# breakoutWithPH.net
KiCad netlist of a schematic drawn in EAGLE
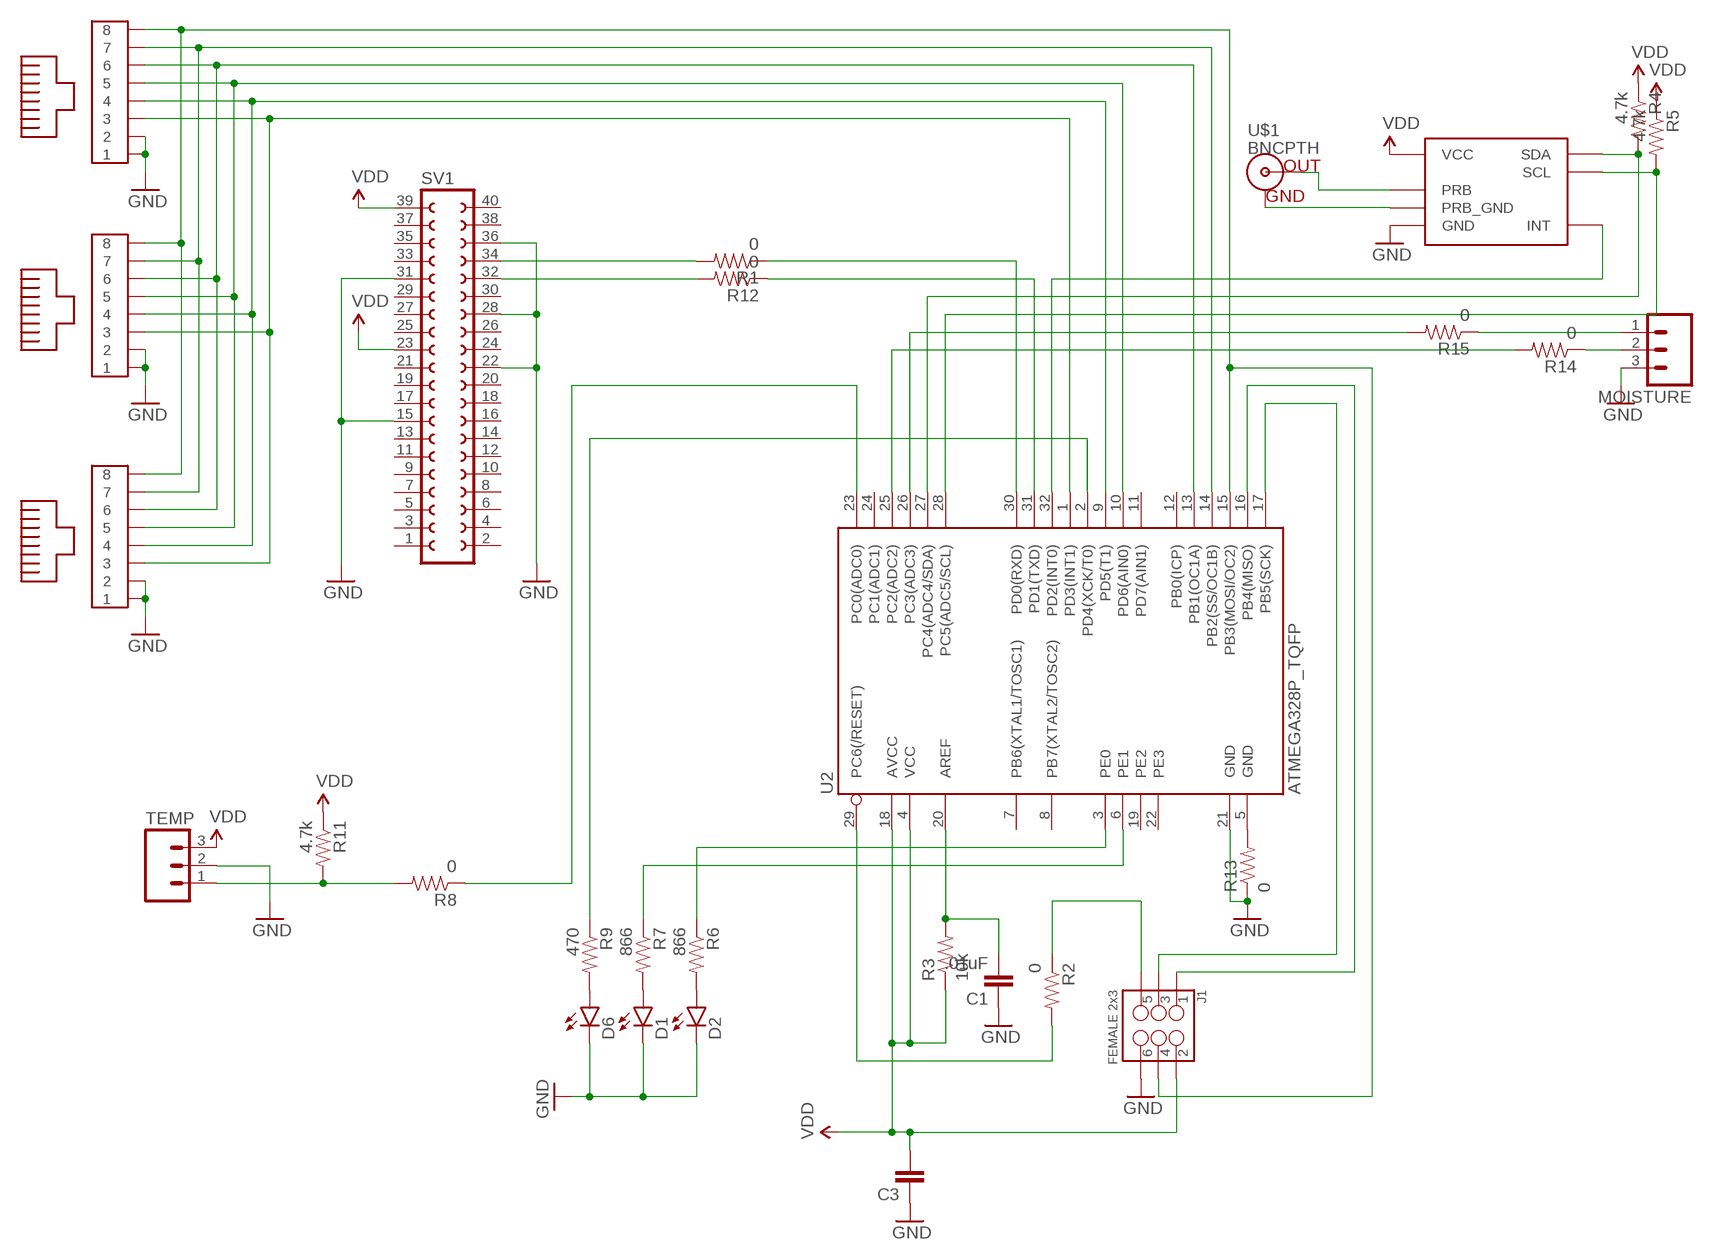
[diagram p0: schematic, sheet 1]

(export (version "E")
  (design (tool "Eeschema 10.0.6"))
  (components
    (comp (ref "C1")
      (value ".01uF")
      (footprint "eagle-import:1206")
      (libsource (lib "eagle-import") (part "CAP1206"))
    )
    (comp (ref "C3")
      (value "CAP1206")
      (footprint "eagle-import:1206")
      (libsource (lib "eagle-import") (part "CAP1206"))
    )
    (comp (ref "D1")
      (value "LED0603")
      (footprint "eagle-import:LED-0603")
      (libsource (lib "eagle-import") (part "LED0603"))
    )
    (comp (ref "D2")
      (value "LED0603")
      (footprint "eagle-import:LED-0603")
      (libsource (lib "eagle-import") (part "LED0603"))
    )
    (comp (ref "D6")
      (value "LED0603")
      (footprint "eagle-import:LED-0603")
      (libsource (lib "eagle-import") (part "LED0603"))
    )
    (comp (ref "J1")
      (value "FEMALE 2x3")
      (footprint "eagle-import:2X3")
      (libsource (lib "eagle-import") (part "M03X2FEMALE"))
    )
    (comp (ref "MOISTURE")
      (value "M03LOCK_LONGPADS")
      (footprint "eagle-import:1X03_LOCK_LONGPADS")
      (libsource (lib "eagle-import") (part "M03LOCK_LONGPADS"))
    )
    (comp (ref "R1")
      (value "0")
      (footprint "eagle-import:1206")
      (libsource (lib "eagle-import") (part "RESISTOR1206"))
    )
    (comp (ref "R2")
      (value "0")
      (footprint "eagle-import:1206")
      (libsource (lib "eagle-import") (part "RESISTOR1206"))
    )
    (comp (ref "R3")
      (value "10k")
      (footprint "eagle-import:1206")
      (libsource (lib "eagle-import") (part "RESISTOR1206"))
    )
    (comp (ref "R4")
      (value "4.7k")
      (footprint "eagle-import:1206")
      (libsource (lib "eagle-import") (part "RESISTOR1206"))
    )
    (comp (ref "R5")
      (value "4.7k")
      (footprint "eagle-import:1206")
      (libsource (lib "eagle-import") (part "RESISTOR1206"))
    )
    (comp (ref "R6")
      (value "866")
      (footprint "eagle-import:1206")
      (libsource (lib "eagle-import") (part "RESISTOR1206"))
    )
    (comp (ref "R7")
      (value "866")
      (footprint "eagle-import:1206")
      (libsource (lib "eagle-import") (part "RESISTOR1206"))
    )
    (comp (ref "R8")
      (value "0")
      (footprint "eagle-import:1206")
      (libsource (lib "eagle-import") (part "RESISTOR1206"))
    )
    (comp (ref "R9")
      (value "470")
      (footprint "eagle-import:1206")
      (libsource (lib "eagle-import") (part "RESISTOR1206"))
    )
    (comp (ref "R11")
      (value "4.7k")
      (footprint "eagle-import:1206")
      (libsource (lib "eagle-import") (part "RESISTOR1206"))
    )
    (comp (ref "R12")
      (value "0")
      (footprint "eagle-import:1206")
      (libsource (lib "eagle-import") (part "RESISTOR1206"))
    )
    (comp (ref "R13")
      (value "0")
      (footprint "eagle-import:1206")
      (libsource (lib "eagle-import") (part "RESISTOR1206"))
    )
    (comp (ref "R14")
      (value "0")
      (footprint "eagle-import:1206")
      (libsource (lib "eagle-import") (part "RESISTOR1206"))
    )
    (comp (ref "R15")
      (value "0")
      (footprint "eagle-import:1206")
      (libsource (lib "eagle-import") (part "RESISTOR1206"))
    )
    (comp (ref "SV1")
      (value "FE20-2")
      (footprint "eagle-import:FE20-2")
      (libsource (lib "eagle-import") (part "FE20-2"))
    )
    (comp (ref "TEMP")
      (value "M03LOCK_LONGPADS")
      (footprint "eagle-import:1X03_LOCK_LONGPADS")
      (libsource (lib "eagle-import") (part "M03LOCK_LONGPADS"))
    )
    (comp (ref "U$1")
      (value "BNCPTH")
      (footprint "eagle-import:BNC")
      (libsource (lib "eagle-import") (part "BNCPTH"))
    )
    (comp (ref "U$2")
      (value "MOLEX-RJ45-SMT")
      (footprint "eagle-import:MOLEX-RJ45-SMT")
      (libsource (lib "eagle-import") (part "MOLEX-RJ45-SMT"))
    )
    (comp (ref "U$3")
      (value "MOLEX-RJ45-SMT")
      (footprint "eagle-import:MOLEX-RJ45-SMT")
      (libsource (lib "eagle-import") (part "MOLEX-RJ45-SMT"))
    )
    (comp (ref "U$4")
      (value "MOLEX-RJ45-SMT")
      (footprint "eagle-import:MOLEX-RJ45-SMT")
      (libsource (lib "eagle-import") (part "MOLEX-RJ45-SMT"))
    )
    (comp (ref "U1")
      (value "PH_SMD")
      (footprint "eagle-import:PH_SMD")
      (libsource (lib "eagle-import") (part "PH_SMD"))
    )
    (comp (ref "U2")
      (value "ATMEGA328P_TQFP")
      (footprint "eagle-import:TQFP32-08")
      (libsource (lib "eagle-import") (part "ATMEGA328P_TQFP"))
    )
  )
  (nets
    (net (code "1") (name "GND") (class "Default")
      (node (ref "C1") (pin "1") (pinfunction "1_1") (pintype "passive"))
      (node (ref "C3") (pin "1") (pinfunction "1_1") (pintype "passive"))
      (node (ref "D1") (pin "C") (pinfunction "C_C") (pintype "passive"))
      (node (ref "D2") (pin "C") (pinfunction "C_C") (pintype "passive"))
      (node (ref "D6") (pin "C") (pinfunction "C_C") (pintype "passive"))
      (node (ref "J1") (pin "6") (pinfunction "6_6") (pintype "bidirectional"))
      (node (ref "MOISTURE") (pin "3") (pinfunction "3_3") (pintype "passive"))
      (node (ref "R13") (pin "1") (pinfunction "1_1") (pintype "passive"))
      (node (ref "SV1") (pin "15") (pinfunction "15_15") (pintype "passive"))
      (node (ref "SV1") (pin "22") (pinfunction "22_22") (pintype "passive"))
      (node (ref "SV1") (pin "28") (pinfunction "28_28") (pintype "passive"))
      (node (ref "SV1") (pin "31") (pinfunction "31_31") (pintype "passive"))
      (node (ref "SV1") (pin "36") (pinfunction "36_36") (pintype "passive"))
      (node (ref "TEMP") (pin "2") (pinfunction "2_2") (pintype "passive"))
      (node (ref "U$2") (pin "1") (pinfunction "1_1") (pintype "bidirectional"))
      (node (ref "U$2") (pin "2") (pinfunction "2_2") (pintype "bidirectional"))
      (node (ref "U$3") (pin "1") (pinfunction "1_1") (pintype "bidirectional"))
      (node (ref "U$3") (pin "2") (pinfunction "2_2") (pintype "bidirectional"))
      (node (ref "U$4") (pin "1") (pinfunction "1_1") (pintype "bidirectional"))
      (node (ref "U$4") (pin "2") (pinfunction "2_2") (pintype "bidirectional"))
      (node (ref "U1") (pin "6") (pinfunction "GND_6") (pintype "power_in"))
      (node (ref "U2") (pin "21") (pinfunction "GND_21") (pintype "bidirectional"))
    )
    (net (code "2") (name "Net-(D1-PadA)") (class "Default")
      (node (ref "D1") (pin "A") (pinfunction "A_A") (pintype "passive"))
      (node (ref "R7") (pin "2") (pinfunction "2_2") (pintype "passive"))
    )
    (net (code "3") (name "Net-(D2-PadA)") (class "Default")
      (node (ref "D2") (pin "A") (pinfunction "A_A") (pintype "passive"))
      (node (ref "R6") (pin "2") (pinfunction "2_2") (pintype "passive"))
    )
    (net (code "4") (name "Net-(D6-PadA)") (class "Default")
      (node (ref "D6") (pin "A") (pinfunction "A_A") (pintype "passive"))
      (node (ref "R9") (pin "2") (pinfunction "2_2") (pintype "passive"))
    )
    (net (code "5") (name "Net-(J1-Pad5)") (class "Default")
      (node (ref "J1") (pin "5") (pinfunction "5_5") (pintype "bidirectional"))
      (node (ref "R2") (pin "1") (pinfunction "1_1") (pintype "passive"))
    )
    (net (code "6") (name "Net-(MOISTURE-Pad1)") (class "Default")
      (node (ref "MOISTURE") (pin "1") (pinfunction "1_1") (pintype "passive"))
      (node (ref "R15") (pin "1") (pinfunction "1_1") (pintype "passive"))
    )
    (net (code "7") (name "Net-(MOISTURE-Pad2)") (class "Default")
      (node (ref "MOISTURE") (pin "2") (pinfunction "2_2") (pintype "passive"))
      (node (ref "R14") (pin "1") (pinfunction "1_1") (pintype "passive"))
    )
    (net (code "8") (name "Net-(R1-Pad2)") (class "Default")
      (node (ref "R1") (pin "2") (pinfunction "2_2") (pintype "passive"))
      (node (ref "SV1") (pin "34") (pinfunction "34_34") (pintype "passive"))
    )
    (net (code "9") (name "Net-(R11-Pad2)") (class "Default")
      (node (ref "R11") (pin "2") (pinfunction "2_2") (pintype "passive"))
      (node (ref "R8") (pin "2") (pinfunction "2_2") (pintype "passive"))
      (node (ref "TEMP") (pin "1") (pinfunction "1_1") (pintype "passive"))
    )
    (net (code "10") (name "Net-(R12-Pad2)") (class "Default")
      (node (ref "R12") (pin "2") (pinfunction "2_2") (pintype "passive"))
      (node (ref "SV1") (pin "32") (pinfunction "32_32") (pintype "passive"))
    )
    (net (code "11") (name "Net-(R13-Pad2)") (class "Default")
      (node (ref "R13") (pin "2") (pinfunction "2_2") (pintype "passive"))
      (node (ref "U2") (pin "5") (pinfunction "GND_5") (pintype "bidirectional"))
    )
    (net (code "12") (name "Net-(U$1-OUT)") (class "Default")
      (node (ref "U$1") (pin "S") (pinfunction "OUT_S") (pintype "bidirectional"))
      (node (ref "U1") (pin "4") (pinfunction "PRB_4") (pintype "bidirectional"))
    )
    (net (code "13") (name "Net-(U1-INT)") (class "Default")
      (node (ref "U1") (pin "7") (pinfunction "INT_7") (pintype "bidirectional"))
      (node (ref "U2") (pin "32") (pinfunction "PD2(INT0)_32") (pintype "bidirectional"))
    )
    (net (code "14") (name "Net-(U1-PRB_GND)") (class "Default")
      (node (ref "U$1") (pin "GND") (pinfunction "GND_GND") (pintype "bidirectional"))
      (node (ref "U1") (pin "5") (pinfunction "PRB_GND_5") (pintype "power_in"))
    )
    (net (code "15") (name "Net-(U1-SCL)") (class "Default")
      (node (ref "R5") (pin "2") (pinfunction "2_2") (pintype "passive"))
      (node (ref "U1") (pin "8") (pinfunction "SCL_8") (pintype "bidirectional"))
      (node (ref "U2") (pin "28") (pinfunction "PC5(ADC5/SCL)_28") (pintype "bidirectional"))
    )
    (net (code "16") (name "Net-(U1-SDA)") (class "Default")
      (node (ref "R4") (pin "2") (pinfunction "2_2") (pintype "passive"))
      (node (ref "U1") (pin "1") (pinfunction "SDA_1") (pintype "bidirectional"))
      (node (ref "U2") (pin "27") (pinfunction "PC4(ADC4/SDA)_27") (pintype "bidirectional"))
    )
    (net (code "17") (name "Net-(U2-AREF)") (class "Default")
      (node (ref "C1") (pin "2") (pinfunction "2_2") (pintype "passive"))
      (node (ref "R3") (pin "2") (pinfunction "2_2") (pintype "passive"))
      (node (ref "U2") (pin "20") (pinfunction "AREF_20") (pintype "bidirectional"))
    )
    (net (code "18") (name "Net-(U2-PB1(OC1A))") (class "Default")
      (node (ref "U$2") (pin "6") (pinfunction "6_6") (pintype "bidirectional"))
      (node (ref "U$3") (pin "6") (pinfunction "6_6") (pintype "bidirectional"))
      (node (ref "U$4") (pin "6") (pinfunction "6_6") (pintype "bidirectional"))
      (node (ref "U2") (pin "13") (pinfunction "PB1(OC1A)_13") (pintype "bidirectional"))
    )
    (net (code "19") (name "Net-(U2-PB2(SS{slash}OC1B))") (class "Default")
      (node (ref "U$2") (pin "7") (pinfunction "7_7") (pintype "bidirectional"))
      (node (ref "U$3") (pin "7") (pinfunction "7_7") (pintype "bidirectional"))
      (node (ref "U$4") (pin "7") (pinfunction "7_7") (pintype "bidirectional"))
      (node (ref "U2") (pin "14") (pinfunction "PB2(SS/OC1B)_14") (pintype "bidirectional"))
    )
    (net (code "20") (name "Net-(U2-PB3(MOSI{slash}OC2))") (class "Default")
      (node (ref "J1") (pin "4") (pinfunction "4_4") (pintype "bidirectional"))
      (node (ref "U$2") (pin "8") (pinfunction "8_8") (pintype "bidirectional"))
      (node (ref "U$3") (pin "8") (pinfunction "8_8") (pintype "bidirectional"))
      (node (ref "U$4") (pin "8") (pinfunction "8_8") (pintype "bidirectional"))
      (node (ref "U2") (pin "15") (pinfunction "PB3(MOSI/OC2)_15") (pintype "bidirectional"))
    )
    (net (code "21") (name "Net-(U2-PB4(MISO))") (class "Default")
      (node (ref "J1") (pin "1") (pinfunction "1_1") (pintype "bidirectional"))
      (node (ref "U2") (pin "16") (pinfunction "PB4(MISO)_16") (pintype "bidirectional"))
    )
    (net (code "22") (name "Net-(U2-PB5(SCK))") (class "Default")
      (node (ref "J1") (pin "3") (pinfunction "3_3") (pintype "bidirectional"))
      (node (ref "U2") (pin "17") (pinfunction "PB5(SCK)_17") (pintype "bidirectional"))
    )
    (net (code "23") (name "Net-(U2-PC0(ADC0))") (class "Default")
      (node (ref "R8") (pin "1") (pinfunction "1_1") (pintype "passive"))
      (node (ref "U2") (pin "23") (pinfunction "PC0(ADC0)_23") (pintype "bidirectional"))
    )
    (net (code "24") (name "Net-(U2-PC2(ADC2))") (class "Default")
      (node (ref "R14") (pin "2") (pinfunction "2_2") (pintype "passive"))
      (node (ref "U2") (pin "25") (pinfunction "PC2(ADC2)_25") (pintype "bidirectional"))
    )
    (net (code "25") (name "Net-(U2-PC3(ADC3))") (class "Default")
      (node (ref "R15") (pin "2") (pinfunction "2_2") (pintype "passive"))
      (node (ref "U2") (pin "26") (pinfunction "PC3(ADC3)_26") (pintype "bidirectional"))
    )
    (net (code "26") (name "Net-(U2-PC6({slash}RESET))") (class "Default")
      (node (ref "R2") (pin "2") (pinfunction "2_2") (pintype "passive"))
      (node (ref "U2") (pin "29") (pinfunction "PC6(/RESET)_29") (pintype "bidirectional"))
    )
    (net (code "27") (name "Net-(U2-PD0(RXD))") (class "Default")
      (node (ref "R1") (pin "1") (pinfunction "1_1") (pintype "passive"))
      (node (ref "U2") (pin "30") (pinfunction "PD0(RXD)_30") (pintype "bidirectional"))
    )
    (net (code "28") (name "Net-(U2-PD1(TXD))") (class "Default")
      (node (ref "R12") (pin "1") (pinfunction "1_1") (pintype "passive"))
      (node (ref "U2") (pin "31") (pinfunction "PD1(TXD)_31") (pintype "bidirectional"))
    )
    (net (code "29") (name "Net-(U2-PD3(INT1))") (class "Default")
      (node (ref "U$2") (pin "3") (pinfunction "3_3") (pintype "bidirectional"))
      (node (ref "U$3") (pin "3") (pinfunction "3_3") (pintype "bidirectional"))
      (node (ref "U$4") (pin "3") (pinfunction "3_3") (pintype "bidirectional"))
      (node (ref "U2") (pin "1") (pinfunction "PD3(INT1)_1") (pintype "bidirectional"))
    )
    (net (code "30") (name "Net-(U2-PD4(XCK{slash}T0))") (class "Default")
      (node (ref "R9") (pin "1") (pinfunction "1_1") (pintype "passive"))
      (node (ref "U2") (pin "2") (pinfunction "PD4(XCK/T0)_2") (pintype "bidirectional"))
    )
    (net (code "31") (name "Net-(U2-PD5(T1))") (class "Default")
      (node (ref "U$2") (pin "4") (pinfunction "4_4") (pintype "bidirectional"))
      (node (ref "U$3") (pin "4") (pinfunction "4_4") (pintype "bidirectional"))
      (node (ref "U$4") (pin "4") (pinfunction "4_4") (pintype "bidirectional"))
      (node (ref "U2") (pin "9") (pinfunction "PD5(T1)_9") (pintype "bidirectional"))
    )
    (net (code "32") (name "Net-(U2-PD6(AIN0))") (class "Default")
      (node (ref "U$2") (pin "5") (pinfunction "5_5") (pintype "bidirectional"))
      (node (ref "U$3") (pin "5") (pinfunction "5_5") (pintype "bidirectional"))
      (node (ref "U$4") (pin "5") (pinfunction "5_5") (pintype "bidirectional"))
      (node (ref "U2") (pin "10") (pinfunction "PD6(AIN0)_10") (pintype "bidirectional"))
    )
    (net (code "33") (name "Net-(U2-PE0)") (class "Default")
      (node (ref "R6") (pin "1") (pinfunction "1_1") (pintype "passive"))
      (node (ref "U2") (pin "3") (pinfunction "PE0_3") (pintype "bidirectional"))
    )
    (net (code "34") (name "Net-(U2-PE1)") (class "Default")
      (node (ref "R7") (pin "1") (pinfunction "1_1") (pintype "passive"))
      (node (ref "U2") (pin "6") (pinfunction "PE1_6") (pintype "bidirectional"))
    )
    (net (code "35") (name "VDD") (class "Default")
      (node (ref "C3") (pin "2") (pinfunction "2_2") (pintype "passive"))
      (node (ref "J1") (pin "2") (pinfunction "2_2") (pintype "bidirectional"))
      (node (ref "R11") (pin "1") (pinfunction "1_1") (pintype "passive"))
      (node (ref "R3") (pin "1") (pinfunction "1_1") (pintype "passive"))
      (node (ref "R4") (pin "1") (pinfunction "1_1") (pintype "passive"))
      (node (ref "R5") (pin "1") (pinfunction "1_1") (pintype "passive"))
      (node (ref "SV1") (pin "23") (pinfunction "23_23") (pintype "passive"))
      (node (ref "SV1") (pin "39") (pinfunction "39_39") (pintype "passive"))
      (node (ref "TEMP") (pin "3") (pinfunction "3_3") (pintype "passive"))
      (node (ref "U1") (pin "3") (pinfunction "VCC_3") (pintype "power_in"))
      (node (ref "U2") (pin "18") (pinfunction "AVCC_18") (pintype "bidirectional"))
      (node (ref "U2") (pin "4") (pinfunction "VCC_4") (pintype "bidirectional"))
    )
    (net (code "36") (name "unconnected-(SV1-Pad1)") (class "Default")
      (node (ref "SV1") (pin "1") (pinfunction "1_1") (pintype "passive"))
    )
    (net (code "37") (name "unconnected-(SV1-Pad2)") (class "Default")
      (node (ref "SV1") (pin "2") (pinfunction "2_2") (pintype "passive"))
    )
    (net (code "38") (name "unconnected-(SV1-Pad3)") (class "Default")
      (node (ref "SV1") (pin "3") (pinfunction "3_3") (pintype "passive"))
    )
    (net (code "39") (name "unconnected-(SV1-Pad4)") (class "Default")
      (node (ref "SV1") (pin "4") (pinfunction "4_4") (pintype "passive"))
    )
    (net (code "40") (name "unconnected-(SV1-Pad5)") (class "Default")
      (node (ref "SV1") (pin "5") (pinfunction "5_5") (pintype "passive"))
    )
    (net (code "41") (name "unconnected-(SV1-Pad6)") (class "Default")
      (node (ref "SV1") (pin "6") (pinfunction "6_6") (pintype "passive"))
    )
    (net (code "42") (name "unconnected-(SV1-Pad7)") (class "Default")
      (node (ref "SV1") (pin "7") (pinfunction "7_7") (pintype "passive"))
    )
    (net (code "43") (name "unconnected-(SV1-Pad8)") (class "Default")
      (node (ref "SV1") (pin "8") (pinfunction "8_8") (pintype "passive"))
    )
    (net (code "44") (name "unconnected-(SV1-Pad9)") (class "Default")
      (node (ref "SV1") (pin "9") (pinfunction "9_9") (pintype "passive"))
    )
    (net (code "45") (name "unconnected-(SV1-Pad10)") (class "Default")
      (node (ref "SV1") (pin "10") (pinfunction "10_10") (pintype "passive"))
    )
    (net (code "46") (name "unconnected-(SV1-Pad11)") (class "Default")
      (node (ref "SV1") (pin "11") (pinfunction "11_11") (pintype "passive"))
    )
    (net (code "47") (name "unconnected-(SV1-Pad12)") (class "Default")
      (node (ref "SV1") (pin "12") (pinfunction "12_12") (pintype "passive"))
    )
    (net (code "48") (name "unconnected-(SV1-Pad13)") (class "Default")
      (node (ref "SV1") (pin "13") (pinfunction "13_13") (pintype "passive"))
    )
    (net (code "49") (name "unconnected-(SV1-Pad14)") (class "Default")
      (node (ref "SV1") (pin "14") (pinfunction "14_14") (pintype "passive"))
    )
    (net (code "50") (name "unconnected-(SV1-Pad16)") (class "Default")
      (node (ref "SV1") (pin "16") (pinfunction "16_16") (pintype "passive"))
    )
    (net (code "51") (name "unconnected-(SV1-Pad17)") (class "Default")
      (node (ref "SV1") (pin "17") (pinfunction "17_17") (pintype "passive"))
    )
    (net (code "52") (name "unconnected-(SV1-Pad18)") (class "Default")
      (node (ref "SV1") (pin "18") (pinfunction "18_18") (pintype "passive"))
    )
    (net (code "53") (name "unconnected-(SV1-Pad19)") (class "Default")
      (node (ref "SV1") (pin "19") (pinfunction "19_19") (pintype "passive"))
    )
    (net (code "54") (name "unconnected-(SV1-Pad20)") (class "Default")
      (node (ref "SV1") (pin "20") (pinfunction "20_20") (pintype "passive"))
    )
    (net (code "55") (name "unconnected-(SV1-Pad21)") (class "Default")
      (node (ref "SV1") (pin "21") (pinfunction "21_21") (pintype "passive"))
    )
    (net (code "56") (name "unconnected-(SV1-Pad24)") (class "Default")
      (node (ref "SV1") (pin "24") (pinfunction "24_24") (pintype "passive"))
    )
    (net (code "57") (name "unconnected-(SV1-Pad25)") (class "Default")
      (node (ref "SV1") (pin "25") (pinfunction "25_25") (pintype "passive"))
    )
    (net (code "58") (name "unconnected-(SV1-Pad26)") (class "Default")
      (node (ref "SV1") (pin "26") (pinfunction "26_26") (pintype "passive"))
    )
    (net (code "59") (name "unconnected-(SV1-Pad27)") (class "Default")
      (node (ref "SV1") (pin "27") (pinfunction "27_27") (pintype "passive"))
    )
    (net (code "60") (name "unconnected-(SV1-Pad29)") (class "Default")
      (node (ref "SV1") (pin "29") (pinfunction "29_29") (pintype "passive"))
    )
    (net (code "61") (name "unconnected-(SV1-Pad30)") (class "Default")
      (node (ref "SV1") (pin "30") (pinfunction "30_30") (pintype "passive"))
    )
    (net (code "62") (name "unconnected-(SV1-Pad33)") (class "Default")
      (node (ref "SV1") (pin "33") (pinfunction "33_33") (pintype "passive"))
    )
    (net (code "63") (name "unconnected-(SV1-Pad35)") (class "Default")
      (node (ref "SV1") (pin "35") (pinfunction "35_35") (pintype "passive"))
    )
    (net (code "64") (name "unconnected-(SV1-Pad37)") (class "Default")
      (node (ref "SV1") (pin "37") (pinfunction "37_37") (pintype "passive"))
    )
    (net (code "65") (name "unconnected-(SV1-Pad38)") (class "Default")
      (node (ref "SV1") (pin "38") (pinfunction "38_38") (pintype "passive"))
    )
    (net (code "66") (name "unconnected-(SV1-Pad40)") (class "Default")
      (node (ref "SV1") (pin "40") (pinfunction "40_40") (pintype "passive"))
    )
    (net (code "67") (name "unconnected-(U2-PB0(ICP)-Pad12)") (class "Default")
      (node (ref "U2") (pin "12") (pinfunction "PB0(ICP)_12") (pintype "bidirectional"))
    )
    (net (code "68") (name "unconnected-(U2-PB6(XTAL1{slash}TOSC1)-Pad7)") (class "Default")
      (node (ref "U2") (pin "7") (pinfunction "PB6(XTAL1/TOSC1)_7") (pintype "bidirectional"))
    )
    (net (code "69") (name "unconnected-(U2-PB7(XTAL2{slash}TOSC2)-Pad8)") (class "Default")
      (node (ref "U2") (pin "8") (pinfunction "PB7(XTAL2/TOSC2)_8") (pintype "bidirectional"))
    )
    (net (code "70") (name "unconnected-(U2-PC1(ADC1)-Pad24)") (class "Default")
      (node (ref "U2") (pin "24") (pinfunction "PC1(ADC1)_24") (pintype "bidirectional"))
    )
    (net (code "71") (name "unconnected-(U2-PD7(AIN1)-Pad11)") (class "Default")
      (node (ref "U2") (pin "11") (pinfunction "PD7(AIN1)_11") (pintype "bidirectional"))
    )
    (net (code "72") (name "unconnected-(U2-PE2-Pad19)") (class "Default")
      (node (ref "U2") (pin "19") (pinfunction "PE2_19") (pintype "bidirectional"))
    )
    (net (code "73") (name "unconnected-(U2-PE3-Pad22)") (class "Default")
      (node (ref "U2") (pin "22") (pinfunction "PE3_22") (pintype "bidirectional"))
    )
  )
)
